# Multimode-VCF-LM13600.net
KiCad netlist of a schematic drawn in EAGLE
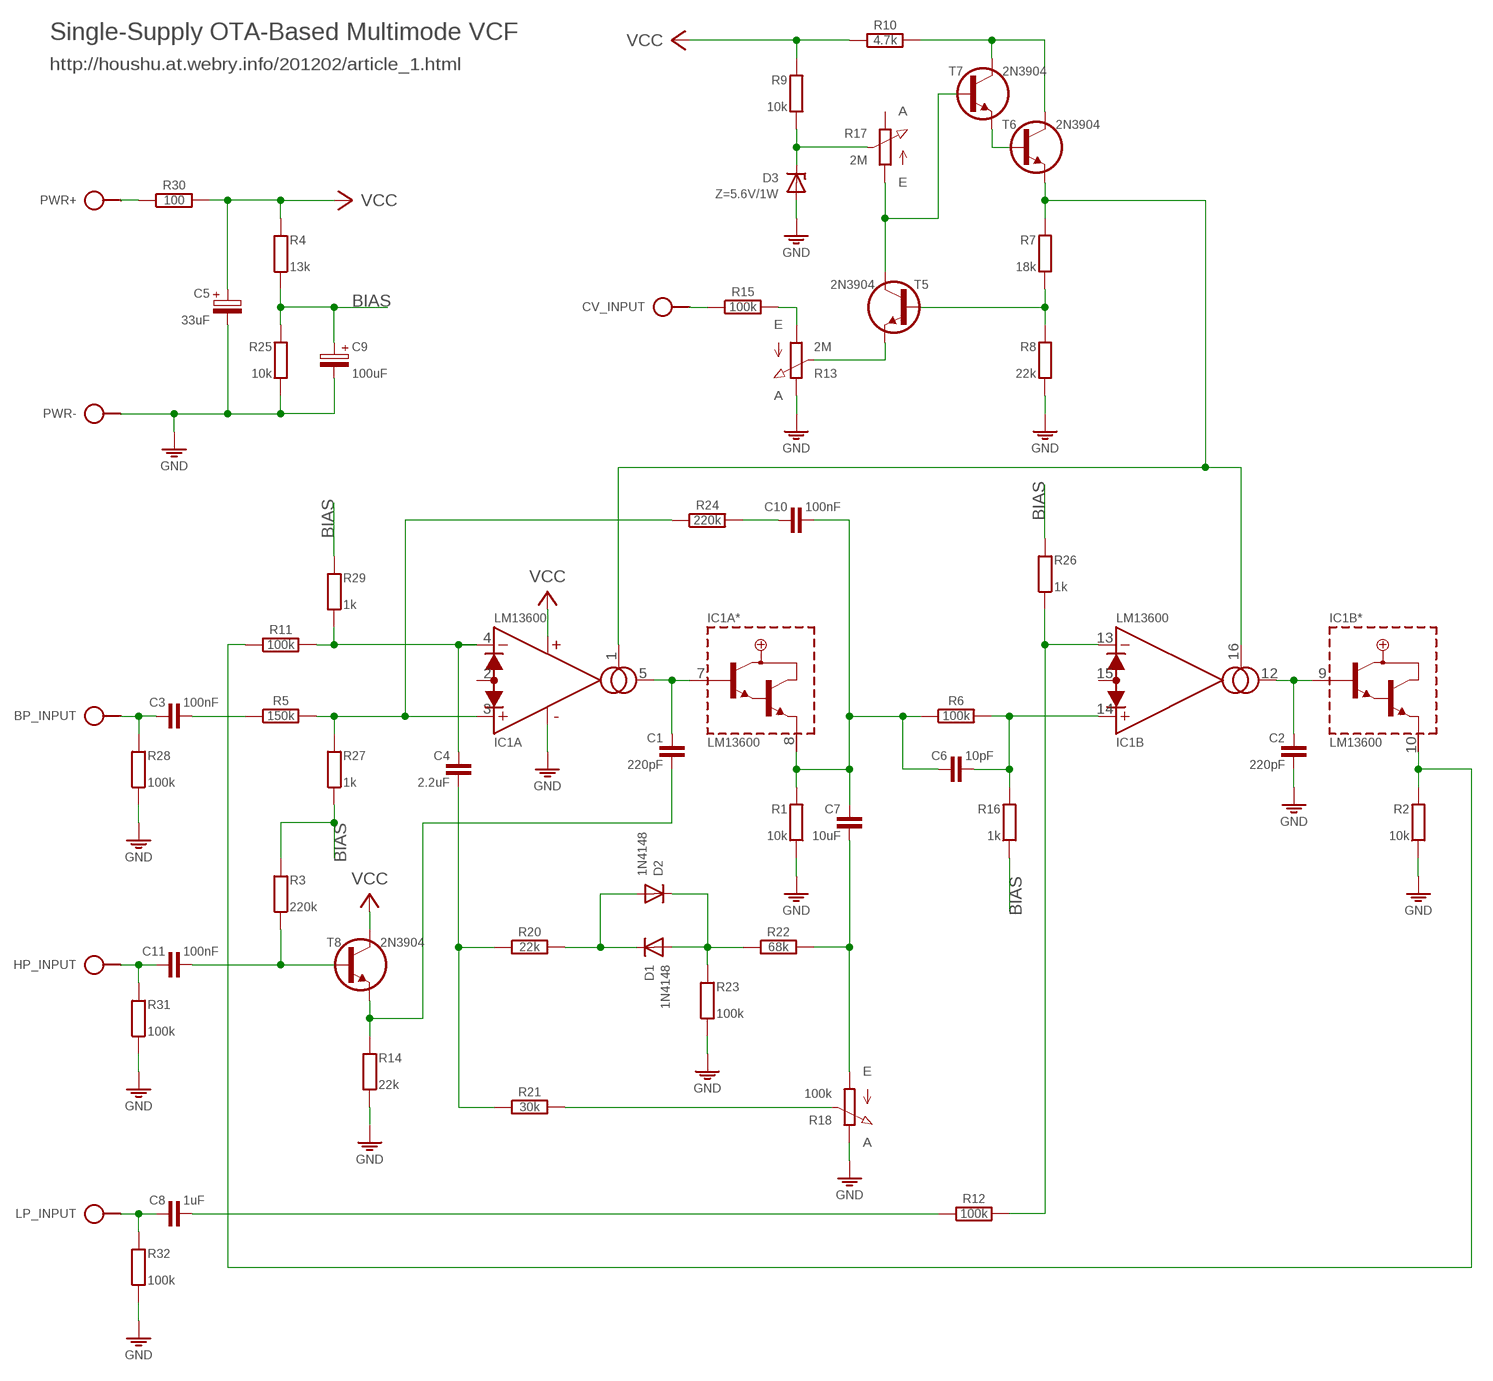
[diagram p0: schematic, sheet 1]

(export (version "E")
  (design (tool "Eeschema 10.0.6"))
  (components
    (comp (ref "BP_INPUT")
      (value "SPAD")
      (footprint "eagle-import:SPAD")
      (libsource (lib "eagle-import") (part "SPAD"))
    )
    (comp (ref "C1")
      (value "220pF")
      (footprint "eagle-import:C050-020X036_V")
      (libsource (lib "eagle-import") (part "C050-020X036/V"))
    )
    (comp (ref "C2")
      (value "220pF")
      (footprint "eagle-import:C050-020X036_V")
      (libsource (lib "eagle-import") (part "C050-020X036/V"))
    )
    (comp (ref "C3")
      (value "100nF")
      (footprint "eagle-import:C050-020X044")
      (libsource (lib "eagle-import") (part "C-H050-020X044"))
    )
    (comp (ref "C4")
      (value "2.2uF")
      (footprint "eagle-import:C050-024X044_V")
      (libsource (lib "eagle-import") (part "C050-024X044/V"))
    )
    (comp (ref "C5")
      (value "33uF")
      (footprint "eagle-import:E2.5-4_V")
      (libsource (lib "eagle-import") (part "CPOLE2,5-4/V"))
    )
    (comp (ref "C6")
      (value "10pF")
      (footprint "eagle-import:C050-020X036")
      (libsource (lib "eagle-import") (part "C-H050-020X036"))
    )
    (comp (ref "C7")
      (value "10uF")
      (footprint "eagle-import:C050-020X036_V")
      (libsource (lib "eagle-import") (part "C050-020X036/V"))
    )
    (comp (ref "C8")
      (value "1uF")
      (footprint "eagle-import:C050-024X044")
      (libsource (lib "eagle-import") (part "C-H050-024X044"))
    )
    (comp (ref "C9")
      (value "100uF")
      (footprint "eagle-import:E2.5-4_V")
      (libsource (lib "eagle-import") (part "CPOLE2,5-4/V"))
    )
    (comp (ref "C10")
      (value "100nF")
      (footprint "eagle-import:C050-020X044")
      (libsource (lib "eagle-import") (part "C-H050-020X044"))
    )
    (comp (ref "C11")
      (value "100nF")
      (footprint "eagle-import:C050-020X044_V")
      (libsource (lib "eagle-import") (part "C-H050-020X044/V"))
    )
    (comp (ref "CV_INPUT")
      (value "SPAD")
      (footprint "eagle-import:SPAD")
      (libsource (lib "eagle-import") (part "SPAD"))
    )
    (comp (ref "D1")
      (value "1N4148")
      (footprint "eagle-import:DO34-2,5-A")
      (libsource (lib "eagle-import") (part "1N414834-2,5-A"))
    )
    (comp (ref "D2")
      (value "1N4148")
      (footprint "eagle-import:DO34-2,5")
      (libsource (lib "eagle-import") (part "1N414834-2,5"))
    )
    (comp (ref "D3")
      (value "Z=5.6V/1W")
      (footprint "eagle-import:DO35Z7_V")
      (libsource (lib "eagle-import") (part "Z-DIODE-35Z7/V"))
    )
    (comp (ref "HP_INPUT")
      (value "SPAD")
      (footprint "eagle-import:SPAD")
      (libsource (lib "eagle-import") (part "SPAD"))
    )
    (comp (ref "IC1")
      (value "LM13600")
      (footprint "eagle-import:DIL16")
      (libsource (lib "eagle-import") (part "LM13600"))
    )
    (comp (ref "LP_INPUT")
      (value "SPAD")
      (footprint "eagle-import:SPAD")
      (libsource (lib "eagle-import") (part "SPAD"))
    )
    (comp (ref "PWR")
      (value "SPAD+--+")
      (footprint "eagle-import:SPAD-+")
      (libsource (lib "eagle-import") (part "SPAD+--+"))
    )
    (comp (ref "R1")
      (value "10k")
      (footprint "eagle-import:0204_10-V")
      (libsource (lib "eagle-import") (part "R0204/10-V"))
    )
    (comp (ref "R2")
      (value "10k")
      (footprint "eagle-import:0204_10")
      (libsource (lib "eagle-import") (part "R0204/10"))
    )
    (comp (ref "R3")
      (value "220k")
      (footprint "eagle-import:0204_10-V")
      (libsource (lib "eagle-import") (part "R0204/10-V"))
    )
    (comp (ref "R4")
      (value "13k")
      (footprint "eagle-import:0204_10-V")
      (libsource (lib "eagle-import") (part "R0204/10-V"))
    )
    (comp (ref "R5")
      (value "150k")
      (footprint "eagle-import:0204_10")
      (libsource (lib "eagle-import") (part "R-H0204/10"))
    )
    (comp (ref "R6")
      (value "100k")
      (footprint "eagle-import:0204_7-V")
      (libsource (lib "eagle-import") (part "R-H0204/7-V"))
    )
    (comp (ref "R7")
      (value "18k")
      (footprint "eagle-import:0204_10-V")
      (libsource (lib "eagle-import") (part "R0204/10-V"))
    )
    (comp (ref "R8")
      (value "22k")
      (footprint "eagle-import:0204_10-V")
      (libsource (lib "eagle-import") (part "R0204/10-V"))
    )
    (comp (ref "R9")
      (value "10k")
      (footprint "eagle-import:0204_10-V")
      (libsource (lib "eagle-import") (part "R0204/10-V"))
    )
    (comp (ref "R10")
      (value "4.7k")
      (footprint "eagle-import:0204_10")
      (libsource (lib "eagle-import") (part "R-H0204/10"))
    )
    (comp (ref "R11")
      (value "100k")
      (footprint "eagle-import:0204_10")
      (libsource (lib "eagle-import") (part "R-H0204/10"))
    )
    (comp (ref "R12")
      (value "100k")
      (footprint "eagle-import:0204_10")
      (libsource (lib "eagle-import") (part "R-H0204/10"))
    )
    (comp (ref "R13")
      (value "2M")
      (footprint "eagle-import:POT-V")
      (libsource (lib "eagle-import") (part "POT-V"))
    )
    (comp (ref "R14")
      (value "22k")
      (footprint "eagle-import:0204_10-V")
      (libsource (lib "eagle-import") (part "R0204/10-V"))
    )
    (comp (ref "R15")
      (value "100k")
      (footprint "eagle-import:0204_10")
      (libsource (lib "eagle-import") (part "R-H0204/10"))
    )
    (comp (ref "R16")
      (value "1k")
      (footprint "eagle-import:0204_7-V")
      (libsource (lib "eagle-import") (part "R0204/7-V"))
    )
    (comp (ref "R17")
      (value "2M")
      (footprint "eagle-import:POT-V")
      (libsource (lib "eagle-import") (part "POT-V"))
    )
    (comp (ref "R18")
      (value "100k")
      (footprint "eagle-import:POT")
      (libsource (lib "eagle-import") (part "POT"))
    )
    (comp (ref "R20")
      (value "22k")
      (footprint "eagle-import:0204_10")
      (libsource (lib "eagle-import") (part "R-H0204/10"))
    )
    (comp (ref "R21")
      (value "30k")
      (footprint "eagle-import:0204_10")
      (libsource (lib "eagle-import") (part "R-H0204/10"))
    )
    (comp (ref "R22")
      (value "68k")
      (footprint "eagle-import:0204_10")
      (libsource (lib "eagle-import") (part "R-H0204/10"))
    )
    (comp (ref "R23")
      (value "100k")
      (footprint "eagle-import:0204_10-V")
      (libsource (lib "eagle-import") (part "R0204/10-V"))
    )
    (comp (ref "R24")
      (value "220k")
      (footprint "eagle-import:0204_10-V")
      (libsource (lib "eagle-import") (part "R-H0204/10-V"))
    )
    (comp (ref "R25")
      (value "10k")
      (footprint "eagle-import:0204_10-V")
      (libsource (lib "eagle-import") (part "R0204/10-V"))
    )
    (comp (ref "R26")
      (value "1k")
      (footprint "eagle-import:0204_7")
      (libsource (lib "eagle-import") (part "R0204/7"))
    )
    (comp (ref "R27")
      (value "1k")
      (footprint "eagle-import:0204_10-V")
      (libsource (lib "eagle-import") (part "R0204/10-V"))
    )
    (comp (ref "R28")
      (value "100k")
      (footprint "eagle-import:0204_10-V")
      (libsource (lib "eagle-import") (part "R0204/10-V"))
    )
    (comp (ref "R29")
      (value "1k")
      (footprint "eagle-import:0204_10-V")
      (libsource (lib "eagle-import") (part "R0204/10-V"))
    )
    (comp (ref "R30")
      (value "100")
      (footprint "eagle-import:0204_10")
      (libsource (lib "eagle-import") (part "R-H0204/10"))
    )
    (comp (ref "R31")
      (value "100k")
      (footprint "eagle-import:0204_10-V")
      (libsource (lib "eagle-import") (part "R0204/10-V"))
    )
    (comp (ref "R32")
      (value "100k")
      (footprint "eagle-import:0204_10-V")
      (libsource (lib "eagle-import") (part "R0204/10-V"))
    )
    (comp (ref "T5")
      (value "2N3904")
      (footprint "eagle-import:TO92")
      (libsource (lib "eagle-import") (part "2N3904"))
    )
    (comp (ref "T6")
      (value "2N3904")
      (footprint "eagle-import:TO92")
      (libsource (lib "eagle-import") (part "2N3904"))
    )
    (comp (ref "T7")
      (value "2N3904")
      (footprint "eagle-import:TO92")
      (libsource (lib "eagle-import") (part "2N3904"))
    )
    (comp (ref "T8")
      (value "2N3904")
      (footprint "eagle-import:TO92")
      (libsource (lib "eagle-import") (part "2N3904"))
    )
  )
  (nets
    (net (code "1") (name "/BIAS") (class "Default")
      (node (ref "C9") (pin "+") (pinfunction "+_+") (pintype "passive"))
      (node (ref "R16") (pin "1") (pinfunction "2_1") (pintype "passive"))
      (node (ref "R25") (pin "1") (pinfunction "1_1") (pintype "passive"))
      (node (ref "R26") (pin "2") (pinfunction "1_2") (pintype "passive"))
      (node (ref "R27") (pin "2") (pinfunction "2_2") (pintype "passive"))
      (node (ref "R29") (pin "1") (pinfunction "1_1") (pintype "passive"))
      (node (ref "R3") (pin "1") (pinfunction "1_1") (pintype "passive"))
      (node (ref "R4") (pin "2") (pinfunction "2_2") (pintype "passive"))
    )
    (net (code "2") (name "GND") (class "Default")
      (node (ref "C2") (pin "2") (pinfunction "2_2") (pintype "passive"))
      (node (ref "C5") (pin "-") (pinfunction "-_-") (pintype "passive"))
      (node (ref "C9") (pin "-") (pinfunction "-_-") (pintype "passive"))
      (node (ref "D3") (pin "A") (pinfunction "A_A") (pintype "passive"))
      (node (ref "IC1") (pin "6") (pinfunction "V-_6") (pintype "power_in"))
      (node (ref "PWR") (pin "1") (pinfunction "P$1_1") (pintype "passive"))
      (node (ref "R1") (pin "2") (pinfunction "2_2") (pintype "passive"))
      (node (ref "R13") (pin "E") (pinfunction "E_E") (pintype "passive"))
      (node (ref "R14") (pin "2") (pinfunction "2_2") (pintype "passive"))
      (node (ref "R18") (pin "3") (pinfunction "E_3") (pintype "passive"))
      (node (ref "R2") (pin "1") (pinfunction "2_1") (pintype "passive"))
      (node (ref "R23") (pin "2") (pinfunction "2_2") (pintype "passive"))
      (node (ref "R25") (pin "2") (pinfunction "2_2") (pintype "passive"))
      (node (ref "R28") (pin "2") (pinfunction "2_2") (pintype "passive"))
      (node (ref "R31") (pin "2") (pinfunction "2_2") (pintype "passive"))
      (node (ref "R32") (pin "2") (pinfunction "2_2") (pintype "passive"))
      (node (ref "R8") (pin "2") (pinfunction "2_2") (pintype "passive"))
    )
    (net (code "3") (name "Net-(BP_INPUT-P$1)") (class "Default")
      (node (ref "BP_INPUT") (pin "1") (pinfunction "P$1_1") (pintype "passive"))
      (node (ref "C3") (pin "1") (pinfunction "1_1") (pintype "passive"))
      (node (ref "R28") (pin "1") (pinfunction "1_1") (pintype "passive"))
    )
    (net (code "4") (name "Net-(C3-Pad2)") (class "Default")
      (node (ref "C3") (pin "2") (pinfunction "2_2") (pintype "passive"))
      (node (ref "R5") (pin "1") (pinfunction "1_1") (pintype "passive"))
    )
    (net (code "5") (name "Net-(C4-Pad2)") (class "Default")
      (node (ref "C4") (pin "2") (pinfunction "2_2") (pintype "passive"))
      (node (ref "R20") (pin "1") (pinfunction "1_1") (pintype "passive"))
      (node (ref "R21") (pin "1") (pinfunction "1_1") (pintype "passive"))
    )
    (net (code "6") (name "Net-(C8-Pad2)") (class "Default")
      (node (ref "C8") (pin "2") (pinfunction "2_2") (pintype "passive"))
      (node (ref "R12") (pin "1") (pinfunction "1_1") (pintype "passive"))
    )
    (net (code "7") (name "Net-(C10-Pad1)") (class "Default")
      (node (ref "C10") (pin "1") (pinfunction "1_1") (pintype "passive"))
      (node (ref "R24") (pin "2") (pinfunction "2_2") (pintype "passive"))
    )
    (net (code "8") (name "Net-(CV_INPUT-P$1)") (class "Default")
      (node (ref "CV_INPUT") (pin "1") (pinfunction "P$1_1") (pintype "passive"))
      (node (ref "R15") (pin "1") (pinfunction "1_1") (pintype "passive"))
    )
    (net (code "9") (name "Net-(D1-PadA)") (class "Default")
      (node (ref "D1") (pin "A") (pinfunction "A_A") (pintype "passive"))
      (node (ref "D2") (pin "C") (pinfunction "C_C") (pintype "passive"))
      (node (ref "R22") (pin "1") (pinfunction "1_1") (pintype "passive"))
      (node (ref "R23") (pin "1") (pinfunction "1_1") (pintype "passive"))
    )
    (net (code "10") (name "Net-(D1-PadC)") (class "Default")
      (node (ref "D1") (pin "C") (pinfunction "C_C") (pintype "passive"))
      (node (ref "D2") (pin "A") (pinfunction "A_A") (pintype "passive"))
      (node (ref "R20") (pin "2") (pinfunction "2_2") (pintype "passive"))
    )
    (net (code "11") (name "Net-(D3-PadC)") (class "Default")
      (node (ref "D3") (pin "C") (pinfunction "C_C") (pintype "passive"))
      (node (ref "R17") (pin "S") (pinfunction "S_S") (pintype "passive"))
      (node (ref "R9") (pin "2") (pinfunction "2_2") (pintype "passive"))
    )
    (net (code "12") (name "Net-(HP_INPUT-P$1)") (class "Default")
      (node (ref "C11") (pin "1") (pinfunction "1_1") (pintype "passive"))
      (node (ref "HP_INPUT") (pin "1") (pinfunction "P$1_1") (pintype "passive"))
      (node (ref "R31") (pin "1") (pinfunction "1_1") (pintype "passive"))
    )
    (net (code "13") (name "Net-(IC1A-+IN)") (class "Default")
      (node (ref "IC1") (pin "3") (pinfunction "+IN_3") (pintype "input"))
      (node (ref "R24") (pin "1") (pinfunction "1_1") (pintype "passive"))
      (node (ref "R27") (pin "1") (pinfunction "1_1") (pintype "passive"))
      (node (ref "R5") (pin "2") (pinfunction "2_2") (pintype "passive"))
    )
    (net (code "14") (name "Net-(IC1A--IN)") (class "Default")
      (node (ref "C4") (pin "1") (pinfunction "1_1") (pintype "passive"))
      (node (ref "IC1") (pin "4") (pinfunction "-IN_4") (pintype "input"))
      (node (ref "R11") (pin "2") (pinfunction "2_2") (pintype "passive"))
      (node (ref "R29") (pin "2") (pinfunction "2_2") (pintype "passive"))
    )
    (net (code "15") (name "Net-(IC1A-AMP{slash}BIAS)") (class "Default")
      (node (ref "IC1") (pin "1") (pinfunction "AMP/BIAS_1") (pintype "input"))
      (node (ref "IC1") (pin "16") (pinfunction "AMP/BIAS_16") (pintype "input"))
      (node (ref "R7") (pin "1") (pinfunction "1_1") (pintype "passive"))
      (node (ref "T6") (pin "1") (pinfunction "E_1") (pintype "passive"))
    )
    (net (code "16") (name "Net-(IC1A-OUT)") (class "Default")
      (node (ref "C1") (pin "1") (pinfunction "1_1") (pintype "passive"))
      (node (ref "IC1") (pin "5") (pinfunction "OUT_5") (pintype "output"))
      (node (ref "IC1") (pin "7") (pinfunction "BUFF/IN_7") (pintype "input"))
    )
    (net (code "17") (name "Net-(IC1B-BUFF{slash}OUT)") (class "Default")
      (node (ref "C10") (pin "2") (pinfunction "2_2") (pintype "passive"))
      (node (ref "C6") (pin "1") (pinfunction "1_1") (pintype "passive"))
      (node (ref "C7") (pin "1") (pinfunction "1_1") (pintype "passive"))
      (node (ref "IC1") (pin "8") (pinfunction "BUFF/OUT_8") (pintype "output"))
      (node (ref "R1") (pin "1") (pinfunction "1_1") (pintype "passive"))
      (node (ref "R6") (pin "1") (pinfunction "1_1") (pintype "passive"))
    )
    (net (code "18") (name "Net-(IC1C-+IN)") (class "Default")
      (node (ref "C6") (pin "2") (pinfunction "2_2") (pintype "passive"))
      (node (ref "IC1") (pin "14") (pinfunction "+IN_14") (pintype "input"))
      (node (ref "R16") (pin "2") (pinfunction "1_2") (pintype "passive"))
      (node (ref "R6") (pin "2") (pinfunction "2_2") (pintype "passive"))
    )
    (net (code "19") (name "Net-(IC1C--IN)") (class "Default")
      (node (ref "IC1") (pin "13") (pinfunction "-IN_13") (pintype "input"))
      (node (ref "R12") (pin "2") (pinfunction "2_2") (pintype "passive"))
      (node (ref "R26") (pin "1") (pinfunction "2_1") (pintype "passive"))
    )
    (net (code "20") (name "Net-(IC1C-OUT)") (class "Default")
      (node (ref "C2") (pin "1") (pinfunction "1_1") (pintype "passive"))
      (node (ref "IC1") (pin "12") (pinfunction "OUT_12") (pintype "output"))
      (node (ref "IC1") (pin "9") (pinfunction "BUFF/IN_9") (pintype "input"))
    )
    (net (code "21") (name "Net-(IC1D-BUFF{slash}OUT)") (class "Default")
      (node (ref "IC1") (pin "10") (pinfunction "BUFF/OUT_10") (pintype "output"))
      (node (ref "R11") (pin "1") (pinfunction "1_1") (pintype "passive"))
      (node (ref "R2") (pin "2") (pinfunction "1_2") (pintype "passive"))
    )
    (net (code "22") (name "Net-(LP_INPUT-P$1)") (class "Default")
      (node (ref "C8") (pin "1") (pinfunction "1_1") (pintype "passive"))
      (node (ref "LP_INPUT") (pin "1") (pinfunction "P$1_1") (pintype "passive"))
      (node (ref "R32") (pin "1") (pinfunction "1_1") (pintype "passive"))
    )
    (net (code "23") (name "Net-(PWRA-P$1)") (class "Default")
      (node (ref "PWR") (pin "2") (pinfunction "P$1_2") (pintype "passive"))
      (node (ref "R30") (pin "1") (pinfunction "1_1") (pintype "passive"))
    )
    (net (code "24") (name "Net-(R13-PadA)") (class "Default")
      (node (ref "R13") (pin "A") (pinfunction "A_A") (pintype "passive"))
      (node (ref "R15") (pin "2") (pinfunction "2_2") (pintype "passive"))
    )
    (net (code "25") (name "Net-(R18-A)") (class "Default")
      (node (ref "C7") (pin "2") (pinfunction "2_2") (pintype "passive"))
      (node (ref "R18") (pin "1") (pinfunction "A_1") (pintype "passive"))
      (node (ref "R22") (pin "2") (pinfunction "2_2") (pintype "passive"))
    )
    (net (code "26") (name "Net-(R18-S)") (class "Default")
      (node (ref "R18") (pin "2") (pinfunction "S_2") (pintype "passive"))
      (node (ref "R21") (pin "2") (pinfunction "2_2") (pintype "passive"))
    )
    (net (code "27") (name "Net-(T5-B)") (class "Default")
      (node (ref "R7") (pin "2") (pinfunction "2_2") (pintype "passive"))
      (node (ref "R8") (pin "1") (pinfunction "1_1") (pintype "passive"))
      (node (ref "T5") (pin "2") (pinfunction "B_2") (pintype "passive"))
    )
    (net (code "28") (name "Net-(T5-C)") (class "Default")
      (node (ref "R17") (pin "A") (pinfunction "A_A") (pintype "passive"))
      (node (ref "T5") (pin "3") (pinfunction "C_3") (pintype "passive"))
      (node (ref "T7") (pin "2") (pinfunction "B_2") (pintype "passive"))
    )
    (net (code "29") (name "Net-(T5-E)") (class "Default")
      (node (ref "R13") (pin "S") (pinfunction "S_S") (pintype "passive"))
      (node (ref "T5") (pin "1") (pinfunction "E_1") (pintype "passive"))
    )
    (net (code "30") (name "Net-(T6-B)") (class "Default")
      (node (ref "T6") (pin "2") (pinfunction "B_2") (pintype "passive"))
      (node (ref "T7") (pin "1") (pinfunction "E_1") (pintype "passive"))
    )
    (net (code "31") (name "Net-(T6-C)") (class "Default")
      (node (ref "R10") (pin "2") (pinfunction "2_2") (pintype "passive"))
      (node (ref "T6") (pin "3") (pinfunction "C_3") (pintype "passive"))
      (node (ref "T7") (pin "3") (pinfunction "C_3") (pintype "passive"))
    )
    (net (code "32") (name "Net-(T8-B)") (class "Default")
      (node (ref "C11") (pin "2") (pinfunction "2_2") (pintype "passive"))
      (node (ref "R3") (pin "2") (pinfunction "2_2") (pintype "passive"))
      (node (ref "T8") (pin "2") (pinfunction "B_2") (pintype "passive"))
    )
    (net (code "33") (name "Net-(T8-E)") (class "Default")
      (node (ref "C1") (pin "2") (pinfunction "2_2") (pintype "passive"))
      (node (ref "R14") (pin "1") (pinfunction "1_1") (pintype "passive"))
      (node (ref "T8") (pin "1") (pinfunction "E_1") (pintype "passive"))
    )
    (net (code "34") (name "VCC") (class "Default")
      (node (ref "C5") (pin "+") (pinfunction "+_+") (pintype "passive"))
      (node (ref "IC1") (pin "11") (pinfunction "V+_11") (pintype "power_in"))
      (node (ref "R10") (pin "1") (pinfunction "1_1") (pintype "passive"))
      (node (ref "R30") (pin "2") (pinfunction "2_2") (pintype "passive"))
      (node (ref "R4") (pin "1") (pinfunction "1_1") (pintype "passive"))
      (node (ref "R9") (pin "1") (pinfunction "1_1") (pintype "passive"))
      (node (ref "T8") (pin "3") (pinfunction "C_3") (pintype "passive"))
    )
    (net (code "35") (name "unconnected-(IC1A-DIODE{slash}BIAS-Pad2)") (class "Default")
      (node (ref "IC1") (pin "2") (pinfunction "DIODE/BIAS_2") (pintype "passive"))
    )
    (net (code "36") (name "unconnected-(IC1C-DIODE{slash}BIAS-Pad15)") (class "Default")
      (node (ref "IC1") (pin "15") (pinfunction "DIODE/BIAS_15") (pintype "passive"))
    )
    (net (code "37") (name "unconnected-(R17-PadE)") (class "Default")
      (node (ref "R17") (pin "E") (pinfunction "E_E") (pintype "passive"))
    )
  )
)
